# 856.net
KiCad netlist of a schematic drawn in Altium Designer
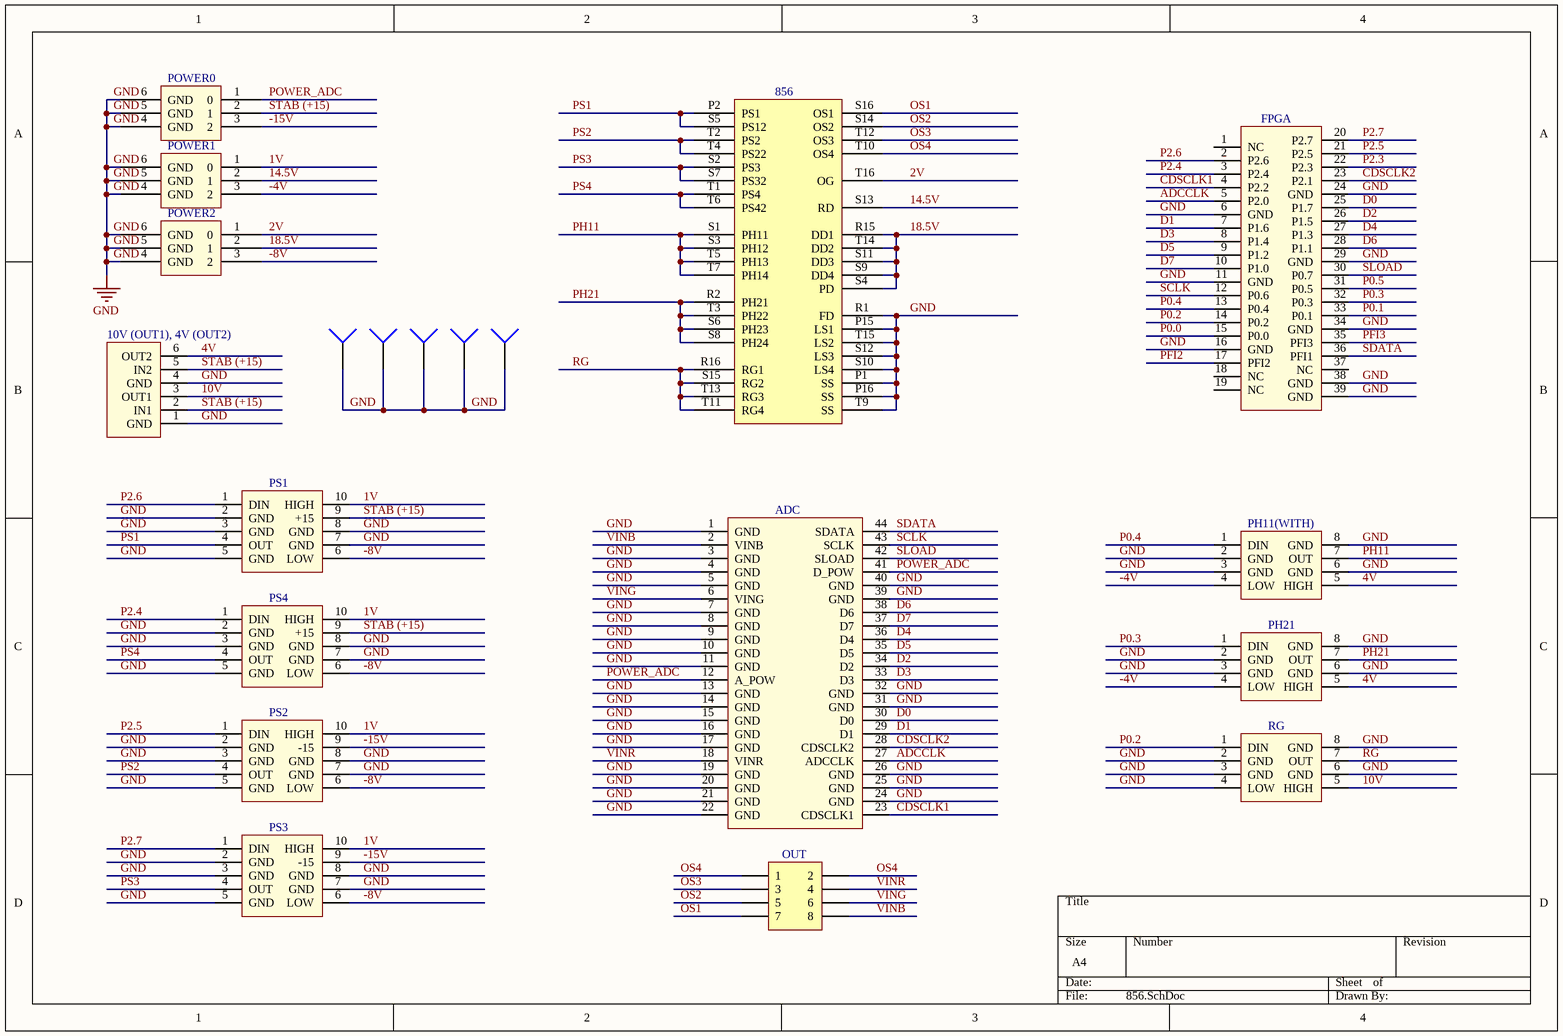
[diagram p0: 856.SchDoc]

(export (version "E")
  (design (tool "Eeschema 10.0.6"))
  (components
    (comp (ref "10V (OUT1), 4V (OUT2)")
      (value "MEZ_POWER")
      (footprint "MEZON_POWER_NEW")
      (libsource (lib "Schlib") (part "MEZON_POWER_NEW"))
    )
    (comp (ref "856")
      (value "Б856А-3")
      (footprint "Dzr_place")
      (libsource (lib "Dzr_SchLib") (part "Б856А-3"))
    )
    (comp (ref "ADC")
      (value "MEZON_ADC")
      (footprint "MEZON_ADC")
      (libsource (lib "Schlib") (part "MEZON_ADC"))
    )
    (comp (ref "FPGA")
      (value "CHEAP_CON_37_FEMALE")
      (footprint "CHEAP_CONN_FEMALE")
      (libsource (lib "Schlib") (part "CHEAP_CON_37_FEMALE"))
    )
    (comp (ref "J1")
      (value "Socket")
      (footprint "PIN1")
      (fields (field (name "PUBLISHER") "Altium Limited"))
      (libsource (lib "Miscellaneous Connectors") (part "Socket"))
    )
    (comp (ref "J2")
      (value "Socket")
      (footprint "PIN1")
      (fields (field (name "PUBLISHER") "Altium Limited"))
      (libsource (lib "Miscellaneous Connectors") (part "Socket"))
    )
    (comp (ref "J3")
      (value "Socket")
      (footprint "PIN1")
      (fields (field (name "PUBLISHER") "Altium Limited"))
      (libsource (lib "Miscellaneous Connectors") (part "Socket"))
    )
    (comp (ref "J4")
      (value "Socket")
      (footprint "PIN1")
      (fields (field (name "PUBLISHER") "Altium Limited"))
      (libsource (lib "Miscellaneous Connectors") (part "Socket"))
    )
    (comp (ref "J5")
      (value "Socket")
      (footprint "PIN1")
      (fields (field (name "PUBLISHER") "Altium Limited"))
      (libsource (lib "Miscellaneous Connectors") (part "Socket"))
    )
    (comp (ref "OUT")
      (value "Header 4X2")
      (footprint "HDR2X4")
      (description "Header, 4-Pin, Dual row")
      (fields (field (name "PUBLISHER") "Altium Limited"))
      (libsource (lib "Miscellaneous Connectors") (part "Header 4X2"))
    )
    (comp (ref "PH11(WITH)")
      (value "MEZON_H")
      (footprint "MEZON_H")
      (libsource (lib "Schlib") (part "MEZON_H"))
    )
    (comp (ref "PH21") (value "MEZON_H") (footprint "MEZON_H") (libsource (lib "Schlib") (part "MEZON_H")))
    (comp (ref "POWER0") (value "POWER") (footprint "POWER") (libsource (lib "Schlib") (part "POWER")))
    (comp (ref "POWER1") (value "POWER") (footprint "POWER") (libsource (lib "Schlib") (part "POWER")))
    (comp (ref "POWER2") (value "POWER") (footprint "POWER") (libsource (lib "Schlib") (part "POWER")))
    (comp (ref "PS1")
      (value "MEZON_V+15")
      (footprint "MEZON_V")
      (libsource (lib "Schlib") (part "MEZON_V_+15"))
    )
    (comp (ref "PS2") (value "MEZON_V") (footprint "MEZON_V") (libsource (lib "Schlib") (part "MEZON_V")))
    (comp (ref "PS3") (value "MEZON_V") (footprint "MEZON_V") (libsource (lib "Schlib") (part "MEZON_V")))
    (comp (ref "PS4")
      (value "MEZON_V+15")
      (footprint "MEZON_V")
      (libsource (lib "Schlib") (part "MEZON_V_+15"))
    )
    (comp (ref "RG") (value "MEZON_H") (footprint "MEZON_H") (libsource (lib "Schlib") (part "MEZON_H")))
  )
  (nets
    (net (code "1") (name "/-4V") (class "Default")
      (node (ref "PH11(WITH)") (pin "4") (pinfunction "LOW_4") (pintype "passive"))
      (node (ref "PH21") (pin "4") (pinfunction "LOW_4") (pintype "passive"))
      (node (ref "POWER1") (pin "3") (pinfunction "2_3") (pintype "passive"))
    )
    (net (code "2") (name "/-8V") (class "Default")
      (node (ref "POWER2") (pin "3") (pinfunction "2_3") (pintype "passive"))
      (node (ref "PS1") (pin "6") (pinfunction "LOW_6") (pintype "passive"))
      (node (ref "PS2") (pin "6") (pinfunction "LOW_6") (pintype "passive"))
      (node (ref "PS3") (pin "6") (pinfunction "LOW_6") (pintype "passive"))
      (node (ref "PS4") (pin "6") (pinfunction "LOW_6") (pintype "passive"))
    )
    (net (code "3") (name "/-15V") (class "Default")
      (node (ref "POWER0") (pin "3") (pinfunction "2_3") (pintype "passive"))
      (node (ref "PS2") (pin "9") (pinfunction "-15_9") (pintype "passive"))
      (node (ref "PS3") (pin "9") (pinfunction "-15_9") (pintype "passive"))
    )
    (net (code "4") (name "/1V") (class "Default")
      (node (ref "POWER1") (pin "1") (pinfunction "0_1") (pintype "passive"))
      (node (ref "PS1") (pin "10") (pinfunction "HIGH_10") (pintype "passive"))
      (node (ref "PS2") (pin "10") (pinfunction "HIGH_10") (pintype "passive"))
      (node (ref "PS3") (pin "10") (pinfunction "HIGH_10") (pintype "passive"))
      (node (ref "PS4") (pin "10") (pinfunction "HIGH_10") (pintype "passive"))
    )
    (net (code "5") (name "/2V") (class "Default")
      (node (ref "856") (pin "T16") (pinfunction "OG_T16") (pintype "passive"))
      (node (ref "POWER2") (pin "1") (pinfunction "0_1") (pintype "passive"))
    )
    (net (code "6") (name "/4V") (class "Default")
      (node (ref "10V (OUT1), 4V (OUT2)") (pin "6") (pinfunction "OUT2_6") (pintype "passive"))
      (node (ref "PH11(WITH)") (pin "5") (pinfunction "HIGH_5") (pintype "passive"))
      (node (ref "PH21") (pin "5") (pinfunction "HIGH_5") (pintype "passive"))
    )
    (net (code "7") (name "/10V") (class "Default")
      (node (ref "10V (OUT1), 4V (OUT2)") (pin "3") (pinfunction "OUT1_3") (pintype "passive"))
      (node (ref "RG") (pin "5") (pinfunction "HIGH_5") (pintype "passive"))
    )
    (net (code "8") (name "/14.5V") (class "Default")
      (node (ref "856") (pin "S13") (pinfunction "RD_S13") (pintype "passive"))
      (node (ref "POWER1") (pin "2") (pinfunction "1_2") (pintype "passive"))
    )
    (net (code "9") (name "/18.5V") (class "Default")
      (node (ref "856") (pin "R15") (pinfunction "DD1_R15") (pintype "passive"))
      (node (ref "856") (pin "S11") (pinfunction "DD3_S11") (pintype "passive"))
      (node (ref "856") (pin "S4") (pinfunction "PD_S4") (pintype "passive"))
      (node (ref "856") (pin "S9") (pinfunction "DD4_S9") (pintype "passive"))
      (node (ref "856") (pin "T14") (pinfunction "DD2_T14") (pintype "passive"))
      (node (ref "POWER2") (pin "2") (pinfunction "1_2") (pintype "passive"))
    )
    (net (code "10") (name "/ADCCLK") (class "Default")
      (node (ref "ADC") (pin "27") (pinfunction "ADCCLK_27") (pintype "passive"))
      (node (ref "FPGA") (pin "5") (pinfunction "P2.0_5") (pintype "passive"))
    )
    (net (code "11") (name "/CDSCLK1") (class "Default")
      (node (ref "ADC") (pin "23") (pinfunction "CDSCLK1_23") (pintype "passive"))
      (node (ref "FPGA") (pin "4") (pinfunction "P2.2_4") (pintype "passive"))
    )
    (net (code "12") (name "/CDSCLK2") (class "Default")
      (node (ref "ADC") (pin "28") (pinfunction "CDSCLK2_28") (pintype "passive"))
      (node (ref "FPGA") (pin "23") (pinfunction "P2.1_23") (pintype "passive"))
    )
    (net (code "13") (name "/D0") (class "Default")
      (node (ref "ADC") (pin "30") (pinfunction "D0_30") (pintype "passive"))
      (node (ref "FPGA") (pin "25") (pinfunction "P1.7_25") (pintype "passive"))
    )
    (net (code "14") (name "/D1") (class "Default")
      (node (ref "ADC") (pin "29") (pinfunction "D1_29") (pintype "passive"))
      (node (ref "FPGA") (pin "7") (pinfunction "P1.6_7") (pintype "passive"))
    )
    (net (code "15") (name "/D2") (class "Default")
      (node (ref "ADC") (pin "34") (pinfunction "D2_34") (pintype "passive"))
      (node (ref "FPGA") (pin "26") (pinfunction "P1.5_26") (pintype "passive"))
    )
    (net (code "16") (name "/D3") (class "Default")
      (node (ref "ADC") (pin "33") (pinfunction "D3_33") (pintype "passive"))
      (node (ref "FPGA") (pin "8") (pinfunction "P1.4_8") (pintype "passive"))
    )
    (net (code "17") (name "/D4") (class "Default")
      (node (ref "ADC") (pin "36") (pinfunction "D4_36") (pintype "passive"))
      (node (ref "FPGA") (pin "27") (pinfunction "P1.3_27") (pintype "passive"))
    )
    (net (code "18") (name "/D5") (class "Default")
      (node (ref "ADC") (pin "35") (pinfunction "D5_35") (pintype "passive"))
      (node (ref "FPGA") (pin "9") (pinfunction "P1.2_9") (pintype "passive"))
    )
    (net (code "19") (name "/D6") (class "Default")
      (node (ref "ADC") (pin "38") (pinfunction "D6_38") (pintype "passive"))
      (node (ref "FPGA") (pin "28") (pinfunction "P1.1_28") (pintype "passive"))
    )
    (net (code "20") (name "/D7") (class "Default")
      (node (ref "ADC") (pin "37") (pinfunction "D7_37") (pintype "passive"))
      (node (ref "FPGA") (pin "10") (pinfunction "P1.0_10") (pintype "passive"))
    )
    (net (code "21") (name "/OS1") (class "Default")
      (node (ref "856") (pin "S16") (pinfunction "OS1_S16") (pintype "passive"))
      (node (ref "OUT") (pin "7") (pinfunction "7_7") (pintype "passive"))
    )
    (net (code "22") (name "/OS2") (class "Default")
      (node (ref "856") (pin "S14") (pinfunction "OS2_S14") (pintype "passive"))
      (node (ref "OUT") (pin "5") (pinfunction "5_5") (pintype "passive"))
    )
    (net (code "23") (name "/OS3") (class "Default")
      (node (ref "856") (pin "T12") (pinfunction "OS3_T12") (pintype "passive"))
      (node (ref "OUT") (pin "3") (pinfunction "3_3") (pintype "passive"))
    )
    (net (code "24") (name "/OS4") (class "Default")
      (node (ref "856") (pin "T10") (pinfunction "OS4_T10") (pintype "passive"))
      (node (ref "OUT") (pin "1") (pinfunction "1_1") (pintype "passive"))
      (node (ref "OUT") (pin "2") (pinfunction "2_2") (pintype "passive"))
    )
    (net (code "25") (name "/P0.0") (class "Default")
      (node (ref "FPGA") (pin "15") (pinfunction "P0.0_15") (pintype "passive"))
    )
    (net (code "26") (name "/P0.1") (class "Default")
      (node (ref "FPGA") (pin "33") (pinfunction "P0.1_33") (pintype "passive"))
    )
    (net (code "27") (name "/P0.2") (class "Default")
      (node (ref "FPGA") (pin "14") (pinfunction "P0.2_14") (pintype "passive"))
      (node (ref "RG") (pin "1") (pinfunction "DIN_1") (pintype "passive"))
    )
    (net (code "28") (name "/P0.3") (class "Default")
      (node (ref "FPGA") (pin "32") (pinfunction "P0.3_32") (pintype "passive"))
      (node (ref "PH21") (pin "1") (pinfunction "DIN_1") (pintype "passive"))
    )
    (net (code "29") (name "/P0.4") (class "Default")
      (node (ref "FPGA") (pin "13") (pinfunction "P0.4_13") (pintype "passive"))
      (node (ref "PH11(WITH)") (pin "1") (pinfunction "DIN_1") (pintype "passive"))
    )
    (net (code "30") (name "/P0.5") (class "Default")
      (node (ref "FPGA") (pin "31") (pinfunction "P0.5_31") (pintype "passive"))
    )
    (net (code "31") (name "/P2.3") (class "Default")
      (node (ref "FPGA") (pin "22") (pinfunction "P2.3_22") (pintype "passive"))
    )
    (net (code "32") (name "/P2.4") (class "Default")
      (node (ref "FPGA") (pin "3") (pinfunction "P2.4_3") (pintype "passive"))
      (node (ref "PS4") (pin "1") (pinfunction "DIN_1") (pintype "passive"))
    )
    (net (code "33") (name "/P2.5") (class "Default")
      (node (ref "FPGA") (pin "21") (pinfunction "P2.5_21") (pintype "passive"))
      (node (ref "PS2") (pin "1") (pinfunction "DIN_1") (pintype "passive"))
    )
    (net (code "34") (name "/P2.6") (class "Default")
      (node (ref "FPGA") (pin "2") (pinfunction "P2.6_2") (pintype "passive"))
      (node (ref "PS1") (pin "1") (pinfunction "DIN_1") (pintype "passive"))
    )
    (net (code "35") (name "/P2.7") (class "Default")
      (node (ref "FPGA") (pin "20") (pinfunction "P2.7_20") (pintype "passive"))
      (node (ref "PS3") (pin "1") (pinfunction "DIN_1") (pintype "passive"))
    )
    (net (code "36") (name "/PFI2") (class "Default")
      (node (ref "FPGA") (pin "17") (pinfunction "PFI2_17") (pintype "passive"))
    )
    (net (code "37") (name "/PFI3") (class "Default")
      (node (ref "FPGA") (pin "35") (pinfunction "PFI3_35") (pintype "passive"))
    )
    (net (code "38") (name "/PH11") (class "Default")
      (node (ref "856") (pin "S1") (pinfunction "PH11_S1") (pintype "passive"))
      (node (ref "856") (pin "S3") (pinfunction "PH12_S3") (pintype "passive"))
      (node (ref "856") (pin "T5") (pinfunction "PH13_T5") (pintype "passive"))
      (node (ref "856") (pin "T7") (pinfunction "PH14_T7") (pintype "passive"))
      (node (ref "PH11(WITH)") (pin "7") (pinfunction "OUT_7") (pintype "passive"))
    )
    (net (code "39") (name "/PH21") (class "Default")
      (node (ref "856") (pin "R2") (pinfunction "PH21_R2") (pintype "passive"))
      (node (ref "856") (pin "S6") (pinfunction "PH23_S6") (pintype "passive"))
      (node (ref "856") (pin "S8") (pinfunction "PH24_S8") (pintype "passive"))
      (node (ref "856") (pin "T3") (pinfunction "PH22_T3") (pintype "passive"))
      (node (ref "PH21") (pin "7") (pinfunction "OUT_7") (pintype "passive"))
    )
    (net (code "40") (name "/POWER_ADC") (class "Default")
      (node (ref "ADC") (pin "12") (pinfunction "A_POW_12") (pintype "passive"))
      (node (ref "ADC") (pin "41") (pinfunction "D_POW_41") (pintype "passive"))
      (node (ref "POWER0") (pin "1") (pinfunction "0_1") (pintype "passive"))
    )
    (net (code "41") (name "/PS1") (class "Default")
      (node (ref "856") (pin "P2") (pinfunction "PS1_P2") (pintype "passive"))
      (node (ref "856") (pin "S5") (pinfunction "PS12_S5") (pintype "passive"))
      (node (ref "PS1") (pin "4") (pinfunction "OUT_4") (pintype "passive"))
    )
    (net (code "42") (name "/PS2") (class "Default")
      (node (ref "856") (pin "T2") (pinfunction "PS2_T2") (pintype "passive"))
      (node (ref "856") (pin "T4") (pinfunction "PS22_T4") (pintype "passive"))
      (node (ref "PS2") (pin "4") (pinfunction "OUT_4") (pintype "passive"))
    )
    (net (code "43") (name "/PS3") (class "Default")
      (node (ref "856") (pin "S2") (pinfunction "PS3_S2") (pintype "passive"))
      (node (ref "856") (pin "S7") (pinfunction "PS32_S7") (pintype "passive"))
      (node (ref "PS3") (pin "4") (pinfunction "OUT_4") (pintype "passive"))
    )
    (net (code "44") (name "/PS4") (class "Default")
      (node (ref "856") (pin "T1") (pinfunction "PS4_T1") (pintype "passive"))
      (node (ref "856") (pin "T6") (pinfunction "PS42_T6") (pintype "passive"))
      (node (ref "PS4") (pin "4") (pinfunction "OUT_4") (pintype "passive"))
    )
    (net (code "45") (name "/RG") (class "Default")
      (node (ref "856") (pin "R16") (pinfunction "RG1_R16") (pintype "passive"))
      (node (ref "856") (pin "S15") (pinfunction "RG2_S15") (pintype "passive"))
      (node (ref "856") (pin "T11") (pinfunction "RG4_T11") (pintype "passive"))
      (node (ref "856") (pin "T13") (pinfunction "RG3_T13") (pintype "passive"))
      (node (ref "RG") (pin "7") (pinfunction "OUT_7") (pintype "passive"))
    )
    (net (code "46") (name "/SCLK") (class "Default")
      (node (ref "ADC") (pin "43") (pinfunction "SCLK_43") (pintype "passive"))
      (node (ref "FPGA") (pin "12") (pinfunction "P0.6_12") (pintype "passive"))
    )
    (net (code "47") (name "/SDATA") (class "Default")
      (node (ref "ADC") (pin "44") (pinfunction "SDATA_44") (pintype "passive"))
      (node (ref "FPGA") (pin "36") (pinfunction "PFI1_36") (pintype "passive"))
    )
    (net (code "48") (name "/SLOAD") (class "Default")
      (node (ref "ADC") (pin "42") (pinfunction "SLOAD_42") (pintype "passive"))
      (node (ref "FPGA") (pin "30") (pinfunction "P0.7_30") (pintype "passive"))
    )
    (net (code "49") (name "/STAB (+15)") (class "Default")
      (node (ref "10V (OUT1), 4V (OUT2)") (pin "2") (pinfunction "IN1_2") (pintype "passive"))
      (node (ref "10V (OUT1), 4V (OUT2)") (pin "5") (pinfunction "IN2_5") (pintype "passive"))
      (node (ref "POWER0") (pin "2") (pinfunction "1_2") (pintype "passive"))
      (node (ref "PS1") (pin "9") (pinfunction "+15_9") (pintype "passive"))
      (node (ref "PS4") (pin "9") (pinfunction "+15_9") (pintype "passive"))
    )
    (net (code "50") (name "/VINB") (class "Default")
      (node (ref "ADC") (pin "2") (pinfunction "VINB_2") (pintype "passive"))
      (node (ref "OUT") (pin "8") (pinfunction "8_8") (pintype "passive"))
    )
    (net (code "51") (name "/VING") (class "Default")
      (node (ref "ADC") (pin "6") (pinfunction "VING_6") (pintype "passive"))
      (node (ref "OUT") (pin "6") (pinfunction "6_6") (pintype "passive"))
    )
    (net (code "52") (name "/VINR") (class "Default")
      (node (ref "ADC") (pin "18") (pinfunction "VINR_18") (pintype "passive"))
      (node (ref "OUT") (pin "4") (pinfunction "4_4") (pintype "passive"))
    )
    (net (code "53") (name "GND") (class "Default")
      (node (ref "10V (OUT1), 4V (OUT2)") (pin "1") (pinfunction "GND_1") (pintype "passive"))
      (node (ref "10V (OUT1), 4V (OUT2)") (pin "4") (pinfunction "GND_4") (pintype "passive"))
      (node (ref "856") (pin "P1") (pinfunction "SS_P1") (pintype "passive"))
      (node (ref "856") (pin "P15") (pinfunction "LS1_P15") (pintype "passive"))
      (node (ref "856") (pin "P16") (pinfunction "SS_P16") (pintype "passive"))
      (node (ref "856") (pin "R1") (pinfunction "FD_R1") (pintype "passive"))
      (node (ref "856") (pin "S10") (pinfunction "LS4_S10") (pintype "passive"))
      (node (ref "856") (pin "S12") (pinfunction "LS3_S12") (pintype "passive"))
      (node (ref "856") (pin "T15") (pinfunction "LS2_T15") (pintype "passive"))
      (node (ref "856") (pin "T9") (pinfunction "SS_T9") (pintype "passive"))
      (node (ref "ADC") (pin "1") (pinfunction "GND_1") (pintype "passive"))
      (node (ref "ADC") (pin "10") (pinfunction "GND_10") (pintype "passive"))
      (node (ref "ADC") (pin "11") (pinfunction "GND_11") (pintype "passive"))
      (node (ref "ADC") (pin "13") (pinfunction "GND_13") (pintype "passive"))
      (node (ref "ADC") (pin "14") (pinfunction "GND_14") (pintype "passive"))
      (node (ref "ADC") (pin "15") (pinfunction "GND_15") (pintype "passive"))
      (node (ref "ADC") (pin "16") (pinfunction "GND_16") (pintype "passive"))
      (node (ref "ADC") (pin "17") (pinfunction "GND_17") (pintype "passive"))
      (node (ref "ADC") (pin "19") (pinfunction "GND_19") (pintype "passive"))
      (node (ref "ADC") (pin "20") (pinfunction "GND_20") (pintype "passive"))
      (node (ref "ADC") (pin "21") (pinfunction "GND_21") (pintype "passive"))
      (node (ref "ADC") (pin "22") (pinfunction "GND_22") (pintype "passive"))
      (node (ref "ADC") (pin "24") (pinfunction "GND_24") (pintype "passive"))
      (node (ref "ADC") (pin "25") (pinfunction "GND_25") (pintype "passive"))
      (node (ref "ADC") (pin "26") (pinfunction "GND_26") (pintype "passive"))
      (node (ref "ADC") (pin "3") (pinfunction "GND_3") (pintype "passive"))
      (node (ref "ADC") (pin "31") (pinfunction "GND_31") (pintype "passive"))
      (node (ref "ADC") (pin "32") (pinfunction "GND_32") (pintype "passive"))
      (node (ref "ADC") (pin "39") (pinfunction "GND_39") (pintype "passive"))
      (node (ref "ADC") (pin "4") (pinfunction "GND_4") (pintype "passive"))
      (node (ref "ADC") (pin "40") (pinfunction "GND_40") (pintype "passive"))
      (node (ref "ADC") (pin "5") (pinfunction "GND_5") (pintype "passive"))
      (node (ref "ADC") (pin "7") (pinfunction "GND_7") (pintype "passive"))
      (node (ref "ADC") (pin "8") (pinfunction "GND_8") (pintype "passive"))
      (node (ref "ADC") (pin "9") (pinfunction "GND_9") (pintype "passive"))
      (node (ref "FPGA") (pin "11") (pinfunction "GND_11") (pintype "passive"))
      (node (ref "FPGA") (pin "16") (pinfunction "GND_16") (pintype "passive"))
      (node (ref "FPGA") (pin "24") (pinfunction "GND_24") (pintype "passive"))
      (node (ref "FPGA") (pin "29") (pinfunction "GND_29") (pintype "passive"))
      (node (ref "FPGA") (pin "34") (pinfunction "GND_34") (pintype "passive"))
      (node (ref "FPGA") (pin "38") (pinfunction "GND_38") (pintype "passive"))
      (node (ref "FPGA") (pin "39") (pinfunction "GND_39") (pintype "passive"))
      (node (ref "FPGA") (pin "6") (pinfunction "GND_6") (pintype "passive"))
      (node (ref "J1") (pin "1") (pinfunction "1_1") (pintype "passive"))
      (node (ref "J2") (pin "1") (pinfunction "1_1") (pintype "passive"))
      (node (ref "J3") (pin "1") (pinfunction "1_1") (pintype "passive"))
      (node (ref "J4") (pin "1") (pinfunction "1_1") (pintype "passive"))
      (node (ref "J5") (pin "1") (pinfunction "1_1") (pintype "passive"))
      (node (ref "PH11(WITH)") (pin "2") (pinfunction "GND_2") (pintype "passive"))
      (node (ref "PH11(WITH)") (pin "3") (pinfunction "GND_3") (pintype "passive"))
      (node (ref "PH11(WITH)") (pin "6") (pinfunction "GND_6") (pintype "passive"))
      (node (ref "PH11(WITH)") (pin "8") (pinfunction "GND_8") (pintype "passive"))
      (node (ref "PH21") (pin "2") (pinfunction "GND_2") (pintype "passive"))
      (node (ref "PH21") (pin "3") (pinfunction "GND_3") (pintype "passive"))
      (node (ref "PH21") (pin "6") (pinfunction "GND_6") (pintype "passive"))
      (node (ref "PH21") (pin "8") (pinfunction "GND_8") (pintype "passive"))
      (node (ref "POWER0") (pin "4") (pinfunction "GND_4") (pintype "passive"))
      (node (ref "POWER0") (pin "5") (pinfunction "GND_5") (pintype "passive"))
      (node (ref "POWER0") (pin "6") (pinfunction "GND_6") (pintype "passive"))
      (node (ref "POWER1") (pin "4") (pinfunction "GND_4") (pintype "passive"))
      (node (ref "POWER1") (pin "5") (pinfunction "GND_5") (pintype "passive"))
      (node (ref "POWER1") (pin "6") (pinfunction "GND_6") (pintype "passive"))
      (node (ref "POWER2") (pin "4") (pinfunction "GND_4") (pintype "passive"))
      (node (ref "POWER2") (pin "5") (pinfunction "GND_5") (pintype "passive"))
      (node (ref "POWER2") (pin "6") (pinfunction "GND_6") (pintype "passive"))
      (node (ref "PS1") (pin "2") (pinfunction "GND_2") (pintype "passive"))
      (node (ref "PS1") (pin "3") (pinfunction "GND_3") (pintype "passive"))
      (node (ref "PS1") (pin "5") (pinfunction "GND_5") (pintype "passive"))
      (node (ref "PS1") (pin "7") (pinfunction "GND_7") (pintype "passive"))
      (node (ref "PS1") (pin "8") (pinfunction "GND_8") (pintype "passive"))
      (node (ref "PS2") (pin "2") (pinfunction "GND_2") (pintype "passive"))
      (node (ref "PS2") (pin "3") (pinfunction "GND_3") (pintype "passive"))
      (node (ref "PS2") (pin "5") (pinfunction "GND_5") (pintype "passive"))
      (node (ref "PS2") (pin "7") (pinfunction "GND_7") (pintype "passive"))
      (node (ref "PS2") (pin "8") (pinfunction "GND_8") (pintype "passive"))
      (node (ref "PS3") (pin "2") (pinfunction "GND_2") (pintype "passive"))
      (node (ref "PS3") (pin "3") (pinfunction "GND_3") (pintype "passive"))
      (node (ref "PS3") (pin "5") (pinfunction "GND_5") (pintype "passive"))
      (node (ref "PS3") (pin "7") (pinfunction "GND_7") (pintype "passive"))
      (node (ref "PS3") (pin "8") (pinfunction "GND_8") (pintype "passive"))
      (node (ref "PS4") (pin "2") (pinfunction "GND_2") (pintype "passive"))
      (node (ref "PS4") (pin "3") (pinfunction "GND_3") (pintype "passive"))
      (node (ref "PS4") (pin "5") (pinfunction "GND_5") (pintype "passive"))
      (node (ref "PS4") (pin "7") (pinfunction "GND_7") (pintype "passive"))
      (node (ref "PS4") (pin "8") (pinfunction "GND_8") (pintype "passive"))
      (node (ref "RG") (pin "2") (pinfunction "GND_2") (pintype "passive"))
      (node (ref "RG") (pin "3") (pinfunction "GND_3") (pintype "passive"))
      (node (ref "RG") (pin "4") (pinfunction "LOW_4") (pintype "passive"))
      (node (ref "RG") (pin "6") (pinfunction "GND_6") (pintype "passive"))
      (node (ref "RG") (pin "8") (pinfunction "GND_8") (pintype "passive"))
    )
    (net (code "54") (name "unconnected-(FPGA-NC-Pad1)") (class "Default")
      (node (ref "FPGA") (pin "1") (pinfunction "NC_1") (pintype "passive"))
    )
    (net (code "55") (name "unconnected-(FPGA-NC-Pad18)") (class "Default")
      (node (ref "FPGA") (pin "18") (pinfunction "NC_18") (pintype "passive"))
    )
    (net (code "56") (name "unconnected-(FPGA-NC-Pad19)") (class "Default")
      (node (ref "FPGA") (pin "19") (pinfunction "NC_19") (pintype "passive"))
    )
    (net (code "57") (name "unconnected-(FPGA-NC-Pad37)") (class "Default")
      (node (ref "FPGA") (pin "37") (pinfunction "NC_37") (pintype "passive"))
    )
  )
)
